# lab9.net
KiCad netlist of a schematic drawn in EAGLE
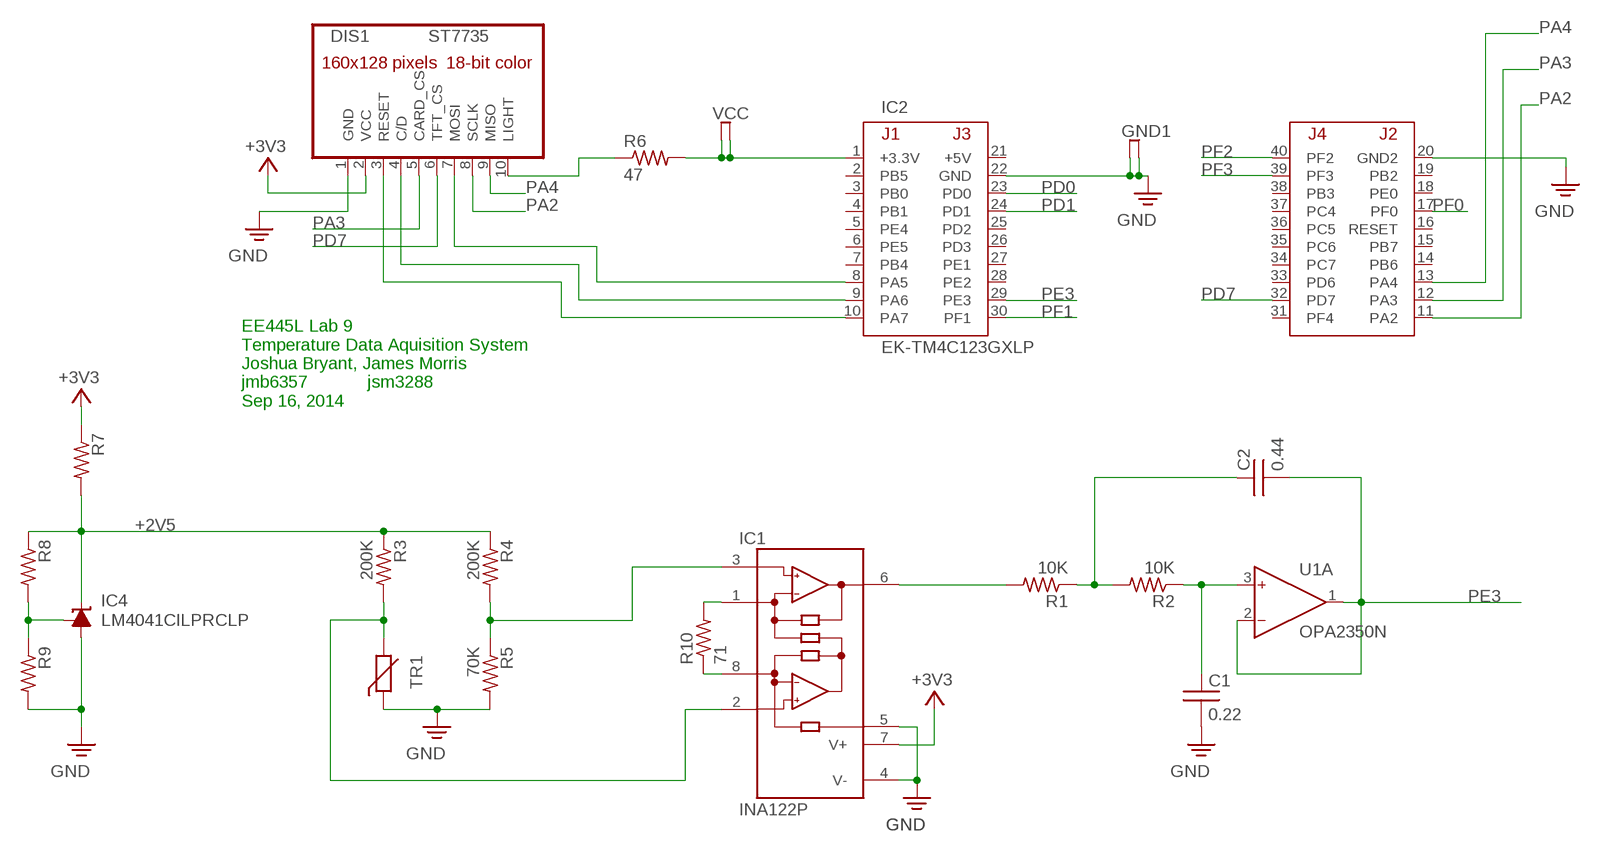
[diagram p0: schematic, sheet 1]

(export (version "E")
  (design (tool "Eeschema 10.0.6"))
  (components
    (comp (ref "C1")
      (value "0.22")
      (footprint "eagle-import:CAP200MIL")
      (libsource (lib "eagle-import") (part "CAPACITOR050-024X044"))
    )
    (comp (ref "C2")
      (value "0.44")
      (footprint "eagle-import:CAP200MIL")
      (libsource (lib "eagle-import") (part "CAPACITOR050-024X044"))
    )
    (comp (ref "DIS1")
      (value "ST7735")
      (footprint "eagle-import:ST7735")
      (libsource (lib "eagle-import") (part "ST7735"))
    )
    (comp (ref "GND1")
      (value "TP2")
      (footprint "eagle-import:TP2")
      (libsource (lib "eagle-import") (part "TP2"))
    )
    (comp (ref "IC1")
      (value "INA122P")
      (footprint "eagle-import:DIL08")
      (fields (field (name "MF") "TEXAS INSTRUMENTS"))
      (libsource (lib "eagle-import") (part "INA122P"))
    )
    (comp (ref "IC2")
      (value "EK-TM4C123GXLP")
      (footprint "eagle-import:TM4C123LAUNCHPAD")
      (libsource (lib "eagle-import") (part "EK-TM4C123GXLP"))
    )
    (comp (ref "IC4")
      (value "LM4041CILPRCLP")
      (footprint "eagle-import:LP_O-PBCY-W3")
      (fields (field (name "MPN") "LM4041CILP"))
      (libsource (lib "eagle-import") (part "LM4041CILPRLPC"))
    )
    (comp (ref "R1")
      (value "10K")
      (footprint "eagle-import:RES300MIL")
      (libsource (lib "eagle-import") (part "RESISTOR0204/7"))
    )
    (comp (ref "R2")
      (value "10K")
      (footprint "eagle-import:RES300MIL")
      (libsource (lib "eagle-import") (part "RESISTOR0204/7"))
    )
    (comp (ref "R3")
      (value "200K")
      (footprint "eagle-import:RES300MIL")
      (libsource (lib "eagle-import") (part "RESISTOR0204/7"))
    )
    (comp (ref "R4")
      (value "200K")
      (footprint "eagle-import:RES300MIL")
      (libsource (lib "eagle-import") (part "RESISTOR0204/7"))
    )
    (comp (ref "R5")
      (value "70K")
      (footprint "eagle-import:RES300MIL")
      (libsource (lib "eagle-import") (part "RESISTOR0204/7"))
    )
    (comp (ref "R6")
      (value "47")
      (footprint "eagle-import:RES_VERTICAL")
      (libsource (lib "eagle-import") (part "RESISTORV526-0"))
    )
    (comp (ref "R7")
      (value "RESISTOR0204/7")
      (footprint "eagle-import:RES300MIL")
      (libsource (lib "eagle-import") (part "RESISTOR0204/7"))
    )
    (comp (ref "R8")
      (value "RESISTOR0204/7")
      (footprint "eagle-import:RES300MIL")
      (libsource (lib "eagle-import") (part "RESISTOR0204/7"))
    )
    (comp (ref "R9")
      (value "RESISTOR0204/7")
      (footprint "eagle-import:RES300MIL")
      (libsource (lib "eagle-import") (part "RESISTOR0204/7"))
    )
    (comp (ref "R10")
      (value "71")
      (footprint "eagle-import:RES300MIL")
      (libsource (lib "eagle-import") (part "RESISTOR0204/7"))
    )
    (comp (ref "TR1")
      (value "THERMISTOR")
      (footprint "eagle-import:1X02")
      (libsource (lib "eagle-import") (part "THERMISTOR"))
    )
    (comp (ref "U1")
      (value "OPA2350N")
      (footprint "eagle-import:DIL08")
      (libsource (lib "eagle-import") (part "OPA2350N"))
    )
    (comp (ref "VCC")
      (value "TP2")
      (footprint "eagle-import:TP2")
      (libsource (lib "eagle-import") (part "TP2"))
    )
  )
  (nets
    (net (code "1") (name "+3V3") (class "Default")
      (node (ref "DIS1") (pin "2") (pinfunction "VCC_2") (pintype "power_in"))
      (node (ref "IC1") (pin "7") (pinfunction "V+_7") (pintype "power_in"))
      (node (ref "R7") (pin "1") (pinfunction "1_1") (pintype "passive"))
    )
    (net (code "2") (name "/+2V5") (class "Default")
      (node (ref "IC4") (pin "2") (pinfunction "C_2") (pintype "passive"))
      (node (ref "R3") (pin "1") (pinfunction "1_1") (pintype "passive"))
      (node (ref "R4") (pin "1") (pinfunction "1_1") (pintype "passive"))
      (node (ref "R7") (pin "2") (pinfunction "2_2") (pintype "passive"))
      (node (ref "R8") (pin "1") (pinfunction "1_1") (pintype "passive"))
    )
    (net (code "3") (name "/+5V") (class "Default")
      (node (ref "IC2") (pin "21") (pinfunction "+5V_21") (pintype "power_in"))
    )
    (net (code "4") (name "/PA2") (class "Default")
      (node (ref "DIS1") (pin "8") (pinfunction "SCLK_8") (pintype "input"))
      (node (ref "IC2") (pin "11") (pinfunction "PA2_11") (pintype "bidirectional"))
    )
    (net (code "5") (name "/PA3") (class "Default")
      (node (ref "DIS1") (pin "5") (pinfunction "CARD_CS_5") (pintype "input"))
      (node (ref "IC2") (pin "12") (pinfunction "PA3_12") (pintype "bidirectional"))
    )
    (net (code "6") (name "/PA4") (class "Default")
      (node (ref "DIS1") (pin "9") (pinfunction "MISO_9") (pintype "output"))
      (node (ref "IC2") (pin "13") (pinfunction "PA4_13") (pintype "bidirectional"))
    )
    (net (code "7") (name "/PD0") (class "Default")
      (node (ref "IC2") (pin "23") (pinfunction "PD0_23") (pintype "bidirectional"))
    )
    (net (code "8") (name "/PD1") (class "Default")
      (node (ref "IC2") (pin "24") (pinfunction "PD1_24") (pintype "bidirectional"))
    )
    (net (code "9") (name "/PD7") (class "Default")
      (node (ref "DIS1") (pin "6") (pinfunction "TFT_CS_6") (pintype "input"))
      (node (ref "IC2") (pin "32") (pinfunction "PD7_32") (pintype "bidirectional"))
    )
    (net (code "10") (name "/PE3") (class "Default")
      (node (ref "C2") (pin "2") (pinfunction "2_2") (pintype "passive"))
      (node (ref "IC2") (pin "29") (pinfunction "PE3_29") (pintype "bidirectional"))
      (node (ref "U1") (pin "1") (pinfunction "OUT_1") (pintype "output"))
      (node (ref "U1") (pin "2") (pinfunction "IN-_2") (pintype "input"))
    )
    (net (code "11") (name "/PF0") (class "Default")
      (node (ref "IC2") (pin "17") (pinfunction "PF0_17") (pintype "bidirectional"))
    )
    (net (code "12") (name "/PF1") (class "Default")
      (node (ref "IC2") (pin "30") (pinfunction "PF1_30") (pintype "bidirectional"))
    )
    (net (code "13") (name "/PF2") (class "Default")
      (node (ref "IC2") (pin "40") (pinfunction "PF2_40") (pintype "bidirectional"))
    )
    (net (code "14") (name "/PF3") (class "Default")
      (node (ref "IC2") (pin "39") (pinfunction "PF3_39") (pintype "bidirectional"))
    )
    (net (code "15") (name "GND") (class "Default")
      (node (ref "C1") (pin "2") (pinfunction "2_2") (pintype "passive"))
      (node (ref "DIS1") (pin "1") (pinfunction "GND_1") (pintype "power_in"))
      (node (ref "GND1") (pin "MP") (pinfunction "TPA_MP") (pintype "passive"))
      (node (ref "GND1") (pin "MP1") (pinfunction "TPB_MP1") (pintype "passive"))
      (node (ref "IC1") (pin "4") (pinfunction "V-_4") (pintype "power_in"))
      (node (ref "IC1") (pin "5") (pinfunction "REF_5") (pintype "passive"))
      (node (ref "IC2") (pin "20") (pinfunction "GND2_20") (pintype "power_in"))
      (node (ref "IC2") (pin "22") (pinfunction "GND_22") (pintype "power_in"))
      (node (ref "IC4") (pin "3") (pinfunction "A_3") (pintype "passive"))
      (node (ref "R5") (pin "2") (pinfunction "2_2") (pintype "passive"))
      (node (ref "R9") (pin "2") (pinfunction "2_2") (pintype "passive"))
      (node (ref "TR1") (pin "1") (pinfunction "1_1") (pintype "passive"))
    )
    (net (code "16") (name "Net-(C2-Pad1)") (class "Default")
      (node (ref "C2") (pin "1") (pinfunction "1_1") (pintype "passive"))
      (node (ref "R1") (pin "1") (pinfunction "1_1") (pintype "passive"))
      (node (ref "R2") (pin "2") (pinfunction "2_2") (pintype "passive"))
    )
    (net (code "17") (name "Net-(DIS1-C{slash}D)") (class "Default")
      (node (ref "DIS1") (pin "4") (pinfunction "C/D_4") (pintype "input"))
      (node (ref "IC2") (pin "9") (pinfunction "PA6_9") (pintype "bidirectional"))
    )
    (net (code "18") (name "Net-(DIS1-LIGHT)") (class "Default")
      (node (ref "DIS1") (pin "10") (pinfunction "LIGHT_10") (pintype "passive"))
      (node (ref "R6") (pin "1") (pinfunction "1_1") (pintype "passive"))
    )
    (net (code "19") (name "Net-(DIS1-MOSI)") (class "Default")
      (node (ref "DIS1") (pin "7") (pinfunction "MOSI_7") (pintype "input"))
      (node (ref "IC2") (pin "8") (pinfunction "PA5_8") (pintype "bidirectional"))
    )
    (net (code "20") (name "Net-(DIS1-RESET)") (class "Default")
      (node (ref "DIS1") (pin "3") (pinfunction "RESET_3") (pintype "input"))
      (node (ref "IC2") (pin "10") (pinfunction "PA7_10") (pintype "bidirectional"))
    )
    (net (code "21") (name "Net-(IC1-+IN)") (class "Default")
      (node (ref "IC1") (pin "3") (pinfunction "+IN_3") (pintype "input"))
      (node (ref "R4") (pin "2") (pinfunction "2_2") (pintype "passive"))
      (node (ref "R5") (pin "1") (pinfunction "1_1") (pintype "passive"))
    )
    (net (code "22") (name "Net-(IC1--IN)") (class "Default")
      (node (ref "IC1") (pin "2") (pinfunction "-IN_2") (pintype "input"))
      (node (ref "R3") (pin "2") (pinfunction "2_2") (pintype "passive"))
      (node (ref "TR1") (pin "2") (pinfunction "2_2") (pintype "passive"))
    )
    (net (code "23") (name "Net-(IC1-OUT)") (class "Default")
      (node (ref "IC1") (pin "6") (pinfunction "OUT_6") (pintype "output"))
      (node (ref "R1") (pin "2") (pinfunction "2_2") (pintype "passive"))
    )
    (net (code "24") (name "Net-(IC1-RG-Pad1)") (class "Default")
      (node (ref "IC1") (pin "1") (pinfunction "RG_1") (pintype "passive"))
      (node (ref "R10") (pin "2") (pinfunction "2_2") (pintype "passive"))
    )
    (net (code "25") (name "Net-(IC1-RG-Pad8)") (class "Default")
      (node (ref "IC1") (pin "8") (pinfunction "RG_8") (pintype "passive"))
      (node (ref "R10") (pin "1") (pinfunction "1_1") (pintype "passive"))
    )
    (net (code "26") (name "Net-(IC2-+3.3V)") (class "Default")
      (node (ref "IC2") (pin "1") (pinfunction "+3.3V_1") (pintype "power_in"))
      (node (ref "R6") (pin "2") (pinfunction "2_2") (pintype "passive"))
      (node (ref "VCC") (pin "MP") (pinfunction "TPA_MP") (pintype "passive"))
      (node (ref "VCC") (pin "MP1") (pinfunction "TPB_MP1") (pintype "passive"))
    )
    (net (code "27") (name "Net-(IC4-FB)") (class "Default")
      (node (ref "IC4") (pin "1") (pinfunction "FB_1") (pintype "passive"))
      (node (ref "R8") (pin "2") (pinfunction "2_2") (pintype "passive"))
      (node (ref "R9") (pin "1") (pinfunction "1_1") (pintype "passive"))
    )
    (net (code "28") (name "Net-(U1A-IN+)") (class "Default")
      (node (ref "C1") (pin "1") (pinfunction "1_1") (pintype "passive"))
      (node (ref "R2") (pin "1") (pinfunction "1_1") (pintype "passive"))
      (node (ref "U1") (pin "3") (pinfunction "IN+_3") (pintype "input"))
    )
    (net (code "29") (name "unconnected-(IC2-PB0-Pad3)") (class "Default")
      (node (ref "IC2") (pin "3") (pinfunction "PB0_3") (pintype "bidirectional"))
    )
    (net (code "30") (name "unconnected-(IC2-PB1-Pad4)") (class "Default")
      (node (ref "IC2") (pin "4") (pinfunction "PB1_4") (pintype "bidirectional"))
    )
    (net (code "31") (name "unconnected-(IC2-PB2-Pad19)") (class "Default")
      (node (ref "IC2") (pin "19") (pinfunction "PB2_19") (pintype "bidirectional"))
    )
    (net (code "32") (name "unconnected-(IC2-PB3-Pad38)") (class "Default")
      (node (ref "IC2") (pin "38") (pinfunction "PB3_38") (pintype "bidirectional"))
    )
    (net (code "33") (name "unconnected-(IC2-PB4-Pad7)") (class "Default")
      (node (ref "IC2") (pin "7") (pinfunction "PB4_7") (pintype "bidirectional"))
    )
    (net (code "34") (name "unconnected-(IC2-PB5-Pad2)") (class "Default")
      (node (ref "IC2") (pin "2") (pinfunction "PB5_2") (pintype "bidirectional"))
    )
    (net (code "35") (name "unconnected-(IC2-PB6-Pad14)") (class "Default")
      (node (ref "IC2") (pin "14") (pinfunction "PB6_14") (pintype "bidirectional"))
    )
    (net (code "36") (name "unconnected-(IC2-PB7-Pad15)") (class "Default")
      (node (ref "IC2") (pin "15") (pinfunction "PB7_15") (pintype "bidirectional"))
    )
    (net (code "37") (name "unconnected-(IC2-PC4-Pad37)") (class "Default")
      (node (ref "IC2") (pin "37") (pinfunction "PC4_37") (pintype "bidirectional"))
    )
    (net (code "38") (name "unconnected-(IC2-PC5-Pad36)") (class "Default")
      (node (ref "IC2") (pin "36") (pinfunction "PC5_36") (pintype "bidirectional"))
    )
    (net (code "39") (name "unconnected-(IC2-PC6-Pad35)") (class "Default")
      (node (ref "IC2") (pin "35") (pinfunction "PC6_35") (pintype "bidirectional"))
    )
    (net (code "40") (name "unconnected-(IC2-PC7-Pad34)") (class "Default")
      (node (ref "IC2") (pin "34") (pinfunction "PC7_34") (pintype "bidirectional"))
    )
    (net (code "41") (name "unconnected-(IC2-PD2-Pad25)") (class "Default")
      (node (ref "IC2") (pin "25") (pinfunction "PD2_25") (pintype "bidirectional"))
    )
    (net (code "42") (name "unconnected-(IC2-PD3-Pad26)") (class "Default")
      (node (ref "IC2") (pin "26") (pinfunction "PD3_26") (pintype "bidirectional"))
    )
    (net (code "43") (name "unconnected-(IC2-PD6-Pad33)") (class "Default")
      (node (ref "IC2") (pin "33") (pinfunction "PD6_33") (pintype "bidirectional"))
    )
    (net (code "44") (name "unconnected-(IC2-PE0-Pad18)") (class "Default")
      (node (ref "IC2") (pin "18") (pinfunction "PE0_18") (pintype "bidirectional"))
    )
    (net (code "45") (name "unconnected-(IC2-PE1-Pad27)") (class "Default")
      (node (ref "IC2") (pin "27") (pinfunction "PE1_27") (pintype "bidirectional"))
    )
    (net (code "46") (name "unconnected-(IC2-PE2-Pad28)") (class "Default")
      (node (ref "IC2") (pin "28") (pinfunction "PE2_28") (pintype "bidirectional"))
    )
    (net (code "47") (name "unconnected-(IC2-PE4-Pad5)") (class "Default")
      (node (ref "IC2") (pin "5") (pinfunction "PE4_5") (pintype "bidirectional"))
    )
    (net (code "48") (name "unconnected-(IC2-PE5-Pad6)") (class "Default")
      (node (ref "IC2") (pin "6") (pinfunction "PE5_6") (pintype "bidirectional"))
    )
    (net (code "49") (name "unconnected-(IC2-PF4-Pad31)") (class "Default")
      (node (ref "IC2") (pin "31") (pinfunction "PF4_31") (pintype "bidirectional"))
    )
    (net (code "50") (name "unconnected-(IC2-RESET-Pad16)") (class "Default")
      (node (ref "IC2") (pin "16") (pinfunction "RESET_16") (pintype "input"))
    )
  )
)
